# 85_SOP8_v3.net
KiCad netlist of a schematic drawn in EAGLE
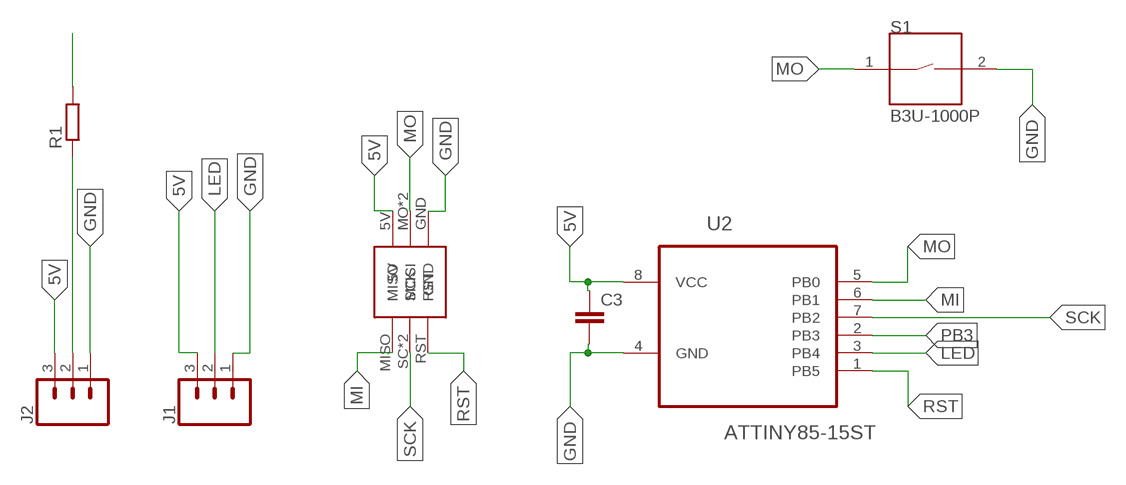
[diagram p0: schematic, sheet 1]

(export (version "E")
  (design (tool "Eeschema 10.0.6"))
  (components
    (comp (ref "C3")
      (value "C-EUC0603")
      (footprint "eagle-import:C0603")
      (libsource (lib "eagle-import") (part "C-EUC0603"))
    )
    (comp (ref "J1")
      (value "CONN_031X03_NO_SILK")
      (footprint "eagle-import:1X03_NO_SILK")
      (libsource (lib "eagle-import") (part "CONN_031X03_NO_SILK"))
    )
    (comp (ref "J2")
      (value "CONN_031X03_NO_SILK")
      (footprint "eagle-import:1X03_NO_SILK")
      (libsource (lib "eagle-import") (part "CONN_031X03_NO_SILK"))
    )
    (comp (ref "R1")
      (value "R-EU_R0603")
      (footprint "eagle-import:R0603")
      (libsource (lib "eagle-import") (part "R-EU_R0603"))
    )
    (comp (ref "S1")
      (value "B3U-1000P")
      (footprint "eagle-import:SW_B3U-1000P")
      (fields (field (name "MF") "Omron"))
      (libsource (lib "eagle-import") (part "B3U-1000P"))
    )
    (comp (ref "U$1")
      (value "ISCP_PORTPOGONEW")
      (footprint "eagle-import:ISCP_PADS_2ROW2HNEW")
      (libsource (lib "eagle-import") (part "ISCP_PORTPOGONEW"))
    )
    (comp (ref "U2")
      (value "ATTINY85-15ST")
      (footprint "eagle-import:SOIC127P798X216-8N")
      (fields (field (name "MF") "Microchip"))
      (libsource (lib "eagle-import") (part "ATTINY85-15ST"))
    )
  )
  (nets
    (net (code "1") (name "5V") (class "Default")
      (node (ref "C3") (pin "1") (pinfunction "1_1") (pintype "passive"))
      (node (ref "J1") (pin "3") (pinfunction "3_3") (pintype "passive"))
      (node (ref "J2") (pin "3") (pinfunction "3_3") (pintype "passive"))
      (node (ref "U$1") (pin "5V") (pinfunction "5V_5V") (pintype "bidirectional"))
      (node (ref "U2") (pin "8") (pinfunction "VCC_8") (pintype "power_in"))
    )
    (net (code "2") (name "GND") (class "Default")
      (node (ref "C3") (pin "2") (pinfunction "2_2") (pintype "passive"))
      (node (ref "J1") (pin "1") (pinfunction "1_1") (pintype "passive"))
      (node (ref "J2") (pin "1") (pinfunction "1_1") (pintype "passive"))
      (node (ref "S1") (pin "2") (pinfunction "2_2") (pintype "passive"))
      (node (ref "U$1") (pin "GND") (pinfunction "GND_GND") (pintype "bidirectional"))
      (node (ref "U2") (pin "4") (pinfunction "GND_4") (pintype "passive"))
    )
    (net (code "3") (name "LED") (class "Default")
      (node (ref "J1") (pin "2") (pinfunction "2_2") (pintype "passive"))
      (node (ref "U2") (pin "3") (pinfunction "PB4_3") (pintype "bidirectional"))
    )
    (net (code "4") (name "MI") (class "Default")
      (node (ref "U$1") (pin "MISO") (pinfunction "MISO_MISO") (pintype "bidirectional"))
      (node (ref "U2") (pin "6") (pinfunction "PB1_6") (pintype "bidirectional"))
    )
    (net (code "5") (name "MO") (class "Default")
      (node (ref "S1") (pin "1") (pinfunction "1_1") (pintype "passive"))
      (node (ref "U$1") (pin "MO") (pinfunction "MOSI_MO") (pintype "bidirectional"))
      (node (ref "U$1") (pin "MOSI") (pinfunction "MOSI_MOSI") (pintype "bidirectional"))
      (node (ref "U2") (pin "5") (pinfunction "PB0_5") (pintype "bidirectional"))
    )
    (net (code "6") (name "Net-(J2-Pad2)") (class "Default")
      (node (ref "J2") (pin "2") (pinfunction "2_2") (pintype "passive"))
      (node (ref "R1") (pin "1") (pinfunction "1_1") (pintype "passive"))
    )
    (net (code "7") (name "PB3") (class "Default")
      (node (ref "U2") (pin "2") (pinfunction "PB3_2") (pintype "bidirectional"))
    )
    (net (code "8") (name "RST") (class "Default")
      (node (ref "U$1") (pin "RST") (pinfunction "RST_RST") (pintype "bidirectional"))
      (node (ref "U2") (pin "1") (pinfunction "PB5_1") (pintype "bidirectional"))
    )
    (net (code "9") (name "SCK") (class "Default")
      (node (ref "R1") (pin "2") (pinfunction "2_2") (pintype "passive"))
      (node (ref "U$1") (pin "SC") (pinfunction "SCK_SC") (pintype "bidirectional"))
      (node (ref "U$1") (pin "SCK") (pinfunction "SCK_SCK") (pintype "bidirectional"))
      (node (ref "U2") (pin "7") (pinfunction "PB2_7") (pintype "bidirectional"))
    )
  )
)
